# SSTuinoII_Jig.net
KiCad netlist of a schematic drawn in EAGLE
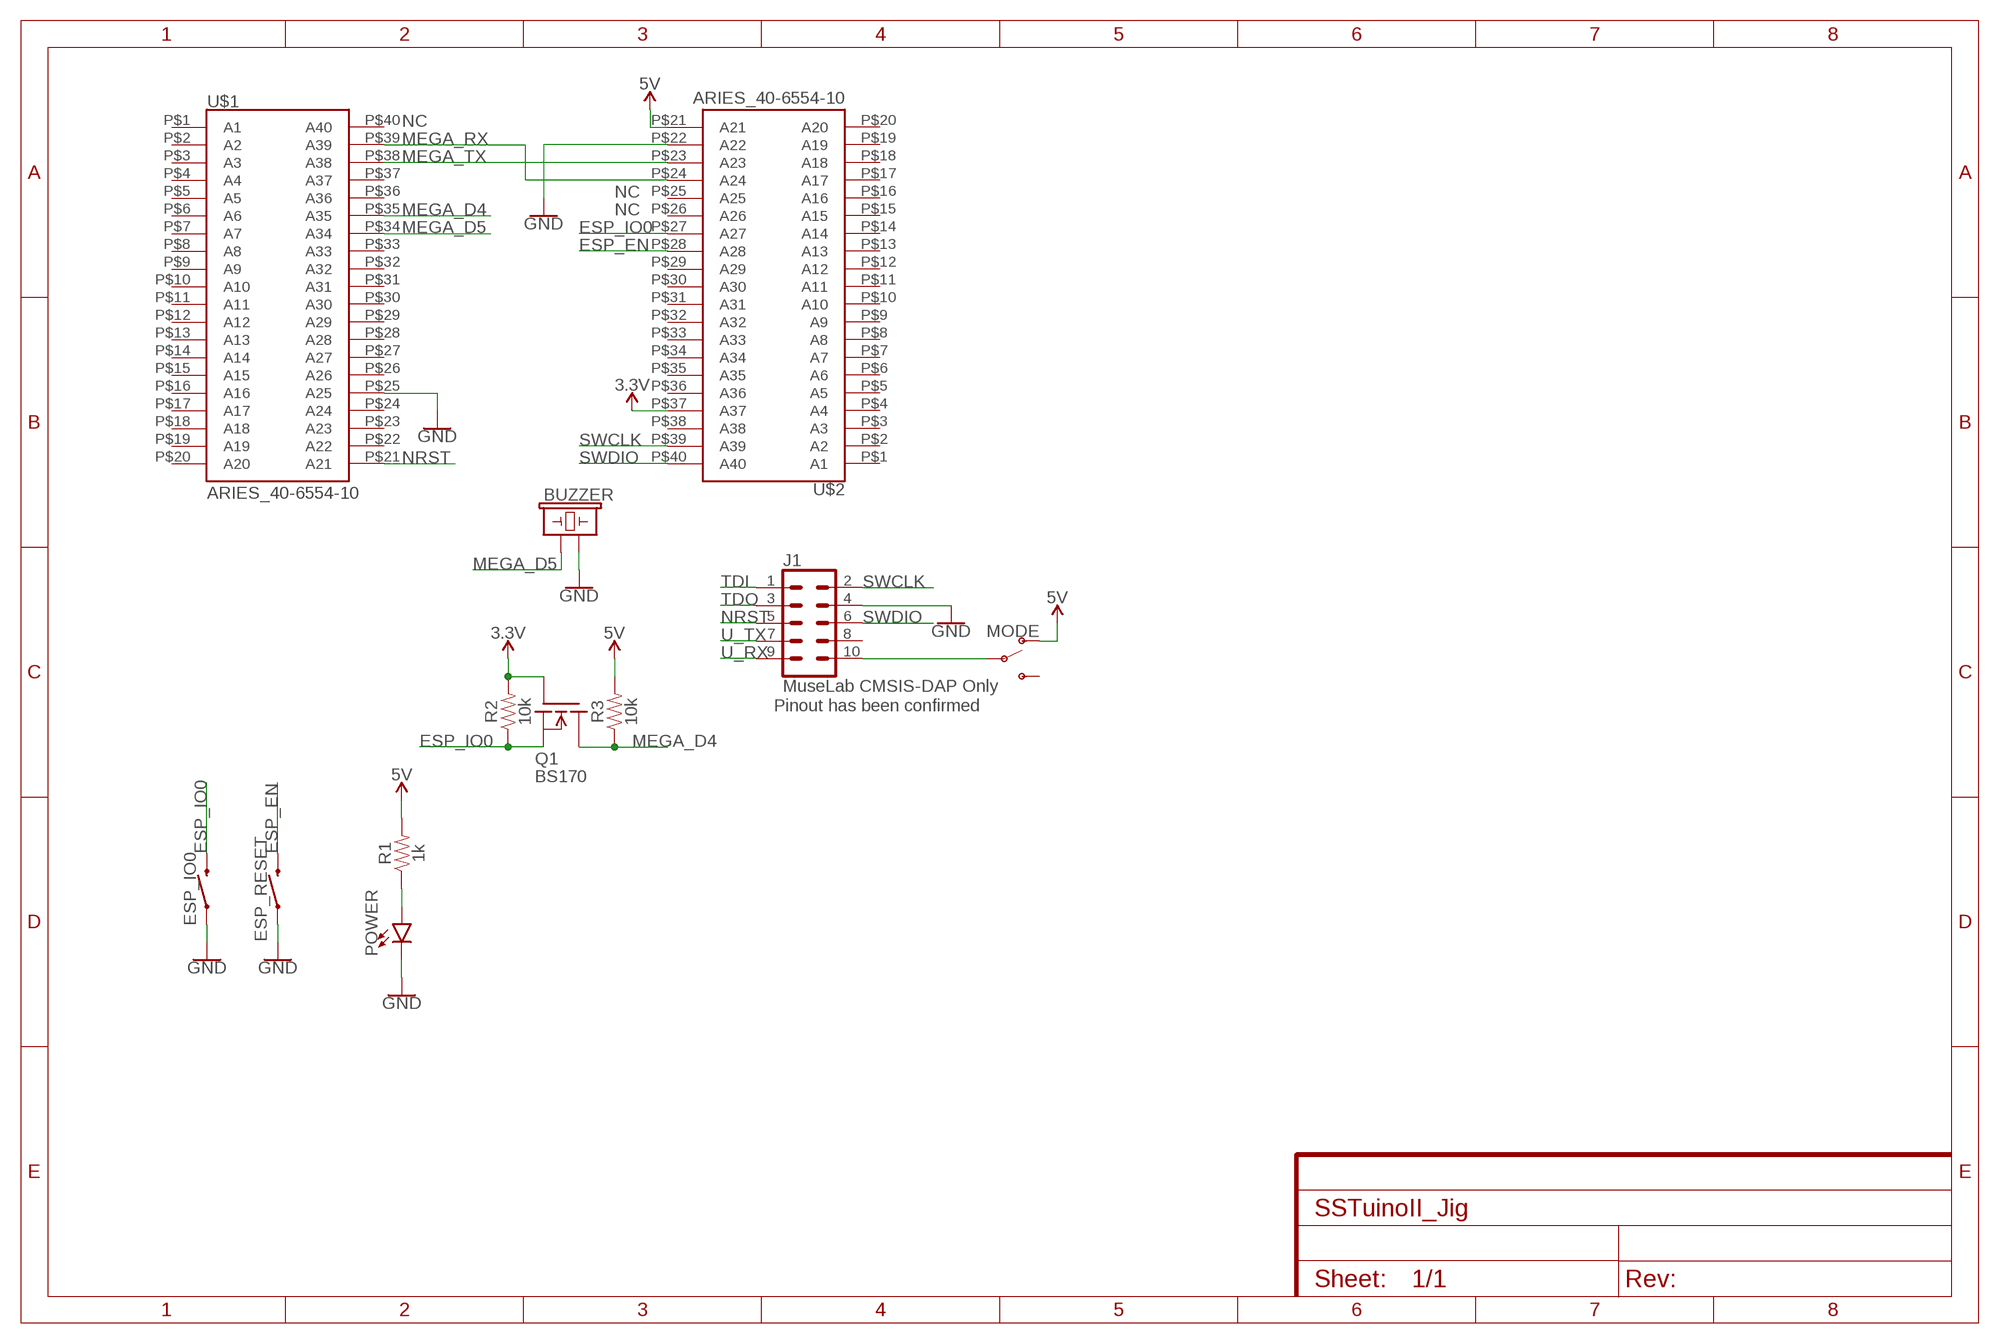
[diagram p0: schematic, sheet 1]

(export (version "E")
  (design (tool "Eeschema 10.0.6"))
  (components
    (comp (ref "BUZZER")
      (value "BUZZER-PTH_KIT")
      (footprint "eagle-import:BUZZER-12MM-KIT")
      (libsource (lib "eagle-import") (part "BUZZER-PTH_KIT"))
    )
    (comp (ref "ESP_IO0")
      (value "MOMENTARY-SWITCH-SPST-PTH-6.0MM-KIT")
      (footprint "eagle-import:TACTILE_SWITCH_PTH_6.0MM_KIT")
      (libsource (lib "eagle-import") (part "MOMENTARY-SWITCH-SPST-PTH-6.0MM-KIT"))
    )
    (comp (ref "ESP_RESET")
      (value "MOMENTARY-SWITCH-SPST-PTH-6.0MM-KIT")
      (footprint "eagle-import:TACTILE_SWITCH_PTH_6.0MM_KIT")
      (libsource (lib "eagle-import") (part "MOMENTARY-SWITCH-SPST-PTH-6.0MM-KIT"))
    )
    (comp (ref "J1")
      (value "MuseLab CMSIS-DAP Only")
      (footprint "eagle-import:2X5-SHROUDED_LOCK")
      (libsource (lib "eagle-import") (part "CONN_05X2SHD_LOCK"))
    )
    (comp (ref "MODE")
      (value "SWITCH-SPDT-PTH-11.6X4.0MM-KIT")
      (footprint "eagle-import:SWITCH_SPDT_PTH_11.6X4.0MM_KIT")
      (libsource (lib "eagle-import") (part "SWITCH-SPDT-PTH-11.6X4.0MM-KIT"))
    )
    (comp (ref "POWER")
      (value "LED3MM")
      (footprint "eagle-import:LED_3MM")
      (libsource (lib "eagle-import") (part "LED3MM"))
    )
    (comp (ref "Q1")
      (value "BS170")
      (footprint "eagle-import:TO92")
      (libsource (lib "eagle-import") (part "BSS101"))
    )
    (comp (ref "R1")
      (value "1k")
      (footprint "eagle-import:AXIAL-0.3-KIT")
      (libsource (lib "eagle-import") (part "1KOHM-HORIZ_KIT-1/4W-1%"))
    )
    (comp (ref "R2")
      (value "10k")
      (footprint "eagle-import:AXIAL-0.3-KIT")
      (libsource (lib "eagle-import") (part "10KOHM-HORIZ_KIT-1/4W-1%"))
    )
    (comp (ref "R3")
      (value "10k")
      (footprint "eagle-import:AXIAL-0.3-KIT")
      (libsource (lib "eagle-import") (part "10KOHM-HORIZ_KIT-1/4W-1%"))
    )
    (comp (ref "U$1")
      (value "ARIES_40-6554-10")
      (footprint "eagle-import:ARIES_40-6554-10")
      (libsource (lib "eagle-import") (part "ARIES_40-6554-10"))
    )
    (comp (ref "U$2")
      (value "ARIES_40-6554-10")
      (footprint "eagle-import:ARIES_40-6554-10")
      (libsource (lib "eagle-import") (part "ARIES_40-6554-10"))
    )
  )
  (nets
    (net (code "1") (name "/ESP_EN") (class "Default")
      (node (ref "ESP_RESET") (pin "3") (pinfunction "2_3") (pintype "passive"))
      (node (ref "U$2") (pin "P$28") (pinfunction "A28_P$28") (pintype "bidirectional"))
    )
    (net (code "2") (name "/ESP_IO0") (class "Default")
      (node (ref "ESP_IO0") (pin "3") (pinfunction "2_3") (pintype "passive"))
      (node (ref "Q1") (pin "1") (pinfunction "S_1") (pintype "passive"))
      (node (ref "R2") (pin "P$1") (pinfunction "1_P$1") (pintype "passive"))
      (node (ref "U$2") (pin "P$27") (pinfunction "A27_P$27") (pintype "bidirectional"))
    )
    (net (code "3") (name "/MEGA_D4") (class "Default")
      (node (ref "Q1") (pin "3") (pinfunction "D_3") (pintype "passive"))
      (node (ref "R3") (pin "P$1") (pinfunction "1_P$1") (pintype "passive"))
      (node (ref "U$1") (pin "P$35") (pinfunction "A35_P$35") (pintype "bidirectional"))
    )
    (net (code "4") (name "/MEGA_D5") (class "Default")
      (node (ref "BUZZER") (pin "+") (pinfunction "1_+") (pintype "passive"))
      (node (ref "U$1") (pin "P$34") (pinfunction "A34_P$34") (pintype "bidirectional"))
    )
    (net (code "5") (name "/MEGA_RX") (class "Default")
      (node (ref "U$1") (pin "P$39") (pinfunction "A39_P$39") (pintype "bidirectional"))
      (node (ref "U$2") (pin "P$24") (pinfunction "A24_P$24") (pintype "bidirectional"))
    )
    (net (code "6") (name "/MEGA_TX") (class "Default")
      (node (ref "U$1") (pin "P$38") (pinfunction "A38_P$38") (pintype "bidirectional"))
      (node (ref "U$2") (pin "P$23") (pinfunction "A23_P$23") (pintype "bidirectional"))
    )
    (net (code "7") (name "/NRST") (class "Default")
      (node (ref "J1") (pin "5") (pinfunction "5_5") (pintype "passive"))
      (node (ref "U$1") (pin "P$21") (pinfunction "A21_P$21") (pintype "bidirectional"))
    )
    (net (code "8") (name "/SWCLK") (class "Default")
      (node (ref "J1") (pin "2") (pinfunction "2_2") (pintype "passive"))
      (node (ref "U$2") (pin "P$39") (pinfunction "A39_P$39") (pintype "bidirectional"))
    )
    (net (code "9") (name "/SWDIO") (class "Default")
      (node (ref "J1") (pin "6") (pinfunction "6_6") (pintype "passive"))
      (node (ref "U$2") (pin "P$40") (pinfunction "A40_P$40") (pintype "bidirectional"))
    )
    (net (code "10") (name "/TDI") (class "Default")
      (node (ref "J1") (pin "1") (pinfunction "1_1") (pintype "passive"))
    )
    (net (code "11") (name "/TDO") (class "Default")
      (node (ref "J1") (pin "3") (pinfunction "3_3") (pintype "passive"))
    )
    (net (code "12") (name "/U_RX") (class "Default")
      (node (ref "J1") (pin "9") (pinfunction "9_9") (pintype "passive"))
    )
    (net (code "13") (name "/U_TX") (class "Default")
      (node (ref "J1") (pin "7") (pinfunction "7_7") (pintype "passive"))
    )
    (net (code "14") (name "3.3V") (class "Default")
      (node (ref "Q1") (pin "2") (pinfunction "G_2") (pintype "passive"))
      (node (ref "R2") (pin "P$2") (pinfunction "2_P$2") (pintype "passive"))
      (node (ref "U$2") (pin "P$37") (pinfunction "A37_P$37") (pintype "bidirectional"))
    )
    (net (code "15") (name "5V") (class "Default")
      (node (ref "MODE") (pin "1") (pinfunction "O_1") (pintype "passive"))
      (node (ref "R1") (pin "P$2") (pinfunction "2_P$2") (pintype "passive"))
      (node (ref "R3") (pin "P$2") (pinfunction "2_P$2") (pintype "passive"))
      (node (ref "U$2") (pin "P$21") (pinfunction "A21_P$21") (pintype "bidirectional"))
    )
    (net (code "16") (name "GND") (class "Default")
      (node (ref "BUZZER") (pin "-") (pinfunction "2_-") (pintype "passive"))
      (node (ref "ESP_IO0") (pin "1") (pinfunction "1_1") (pintype "passive"))
      (node (ref "ESP_RESET") (pin "1") (pinfunction "1_1") (pintype "passive"))
      (node (ref "J1") (pin "4") (pinfunction "4_4") (pintype "passive"))
      (node (ref "POWER") (pin "K") (pinfunction "C_K") (pintype "passive"))
      (node (ref "U$1") (pin "P$25") (pinfunction "A25_P$25") (pintype "bidirectional"))
      (node (ref "U$2") (pin "P$22") (pinfunction "A22_P$22") (pintype "bidirectional"))
    )
    (net (code "17") (name "Net-(MODE-P)") (class "Default")
      (node (ref "J1") (pin "10") (pinfunction "10_10") (pintype "passive"))
      (node (ref "MODE") (pin "2") (pinfunction "P_2") (pintype "passive"))
    )
    (net (code "18") (name "Net-(R1-1)") (class "Default")
      (node (ref "POWER") (pin "A") (pinfunction "A_A") (pintype "passive"))
      (node (ref "R1") (pin "P$1") (pinfunction "1_P$1") (pintype "passive"))
    )
    (net (code "19") (name "unconnected-(J1-Pad8)") (class "Default")
      (node (ref "J1") (pin "8") (pinfunction "8_8") (pintype "passive"))
    )
    (net (code "20") (name "unconnected-(MODE-S-Pad3)") (class "Default")
      (node (ref "MODE") (pin "3") (pinfunction "S_3") (pintype "passive"))
    )
    (net (code "21") (name "unconnected-(U$1-A1-PadP$1)") (class "Default")
      (node (ref "U$1") (pin "P$1") (pinfunction "A1_P$1") (pintype "bidirectional"))
    )
    (net (code "22") (name "unconnected-(U$1-A2-PadP$2)") (class "Default")
      (node (ref "U$1") (pin "P$2") (pinfunction "A2_P$2") (pintype "bidirectional"))
    )
    (net (code "23") (name "unconnected-(U$1-A3-PadP$3)") (class "Default")
      (node (ref "U$1") (pin "P$3") (pinfunction "A3_P$3") (pintype "bidirectional"))
    )
    (net (code "24") (name "unconnected-(U$1-A4-PadP$4)") (class "Default")
      (node (ref "U$1") (pin "P$4") (pinfunction "A4_P$4") (pintype "bidirectional"))
    )
    (net (code "25") (name "unconnected-(U$1-A5-PadP$5)") (class "Default")
      (node (ref "U$1") (pin "P$5") (pinfunction "A5_P$5") (pintype "bidirectional"))
    )
    (net (code "26") (name "unconnected-(U$1-A6-PadP$6)") (class "Default")
      (node (ref "U$1") (pin "P$6") (pinfunction "A6_P$6") (pintype "bidirectional"))
    )
    (net (code "27") (name "unconnected-(U$1-A7-PadP$7)") (class "Default")
      (node (ref "U$1") (pin "P$7") (pinfunction "A7_P$7") (pintype "bidirectional"))
    )
    (net (code "28") (name "unconnected-(U$1-A8-PadP$8)") (class "Default")
      (node (ref "U$1") (pin "P$8") (pinfunction "A8_P$8") (pintype "bidirectional"))
    )
    (net (code "29") (name "unconnected-(U$1-A9-PadP$9)") (class "Default")
      (node (ref "U$1") (pin "P$9") (pinfunction "A9_P$9") (pintype "bidirectional"))
    )
    (net (code "30") (name "unconnected-(U$1-A10-PadP$10)") (class "Default")
      (node (ref "U$1") (pin "P$10") (pinfunction "A10_P$10") (pintype "bidirectional"))
    )
    (net (code "31") (name "unconnected-(U$1-A11-PadP$11)") (class "Default")
      (node (ref "U$1") (pin "P$11") (pinfunction "A11_P$11") (pintype "bidirectional"))
    )
    (net (code "32") (name "unconnected-(U$1-A12-PadP$12)") (class "Default")
      (node (ref "U$1") (pin "P$12") (pinfunction "A12_P$12") (pintype "bidirectional"))
    )
    (net (code "33") (name "unconnected-(U$1-A13-PadP$13)") (class "Default")
      (node (ref "U$1") (pin "P$13") (pinfunction "A13_P$13") (pintype "bidirectional"))
    )
    (net (code "34") (name "unconnected-(U$1-A14-PadP$14)") (class "Default")
      (node (ref "U$1") (pin "P$14") (pinfunction "A14_P$14") (pintype "bidirectional"))
    )
    (net (code "35") (name "unconnected-(U$1-A15-PadP$15)") (class "Default")
      (node (ref "U$1") (pin "P$15") (pinfunction "A15_P$15") (pintype "bidirectional"))
    )
    (net (code "36") (name "unconnected-(U$1-A16-PadP$16)") (class "Default")
      (node (ref "U$1") (pin "P$16") (pinfunction "A16_P$16") (pintype "bidirectional"))
    )
    (net (code "37") (name "unconnected-(U$1-A17-PadP$17)") (class "Default")
      (node (ref "U$1") (pin "P$17") (pinfunction "A17_P$17") (pintype "bidirectional"))
    )
    (net (code "38") (name "unconnected-(U$1-A18-PadP$18)") (class "Default")
      (node (ref "U$1") (pin "P$18") (pinfunction "A18_P$18") (pintype "bidirectional"))
    )
    (net (code "39") (name "unconnected-(U$1-A19-PadP$19)") (class "Default")
      (node (ref "U$1") (pin "P$19") (pinfunction "A19_P$19") (pintype "bidirectional"))
    )
    (net (code "40") (name "unconnected-(U$1-A20-PadP$20)") (class "Default")
      (node (ref "U$1") (pin "P$20") (pinfunction "A20_P$20") (pintype "bidirectional"))
    )
    (net (code "41") (name "unconnected-(U$1-A22-PadP$22)") (class "Default")
      (node (ref "U$1") (pin "P$22") (pinfunction "A22_P$22") (pintype "bidirectional"))
    )
    (net (code "42") (name "unconnected-(U$1-A23-PadP$23)") (class "Default")
      (node (ref "U$1") (pin "P$23") (pinfunction "A23_P$23") (pintype "bidirectional"))
    )
    (net (code "43") (name "unconnected-(U$1-A24-PadP$24)") (class "Default")
      (node (ref "U$1") (pin "P$24") (pinfunction "A24_P$24") (pintype "bidirectional"))
    )
    (net (code "44") (name "unconnected-(U$1-A26-PadP$26)") (class "Default")
      (node (ref "U$1") (pin "P$26") (pinfunction "A26_P$26") (pintype "bidirectional"))
    )
    (net (code "45") (name "unconnected-(U$1-A27-PadP$27)") (class "Default")
      (node (ref "U$1") (pin "P$27") (pinfunction "A27_P$27") (pintype "bidirectional"))
    )
    (net (code "46") (name "unconnected-(U$1-A28-PadP$28)") (class "Default")
      (node (ref "U$1") (pin "P$28") (pinfunction "A28_P$28") (pintype "bidirectional"))
    )
    (net (code "47") (name "unconnected-(U$1-A29-PadP$29)") (class "Default")
      (node (ref "U$1") (pin "P$29") (pinfunction "A29_P$29") (pintype "bidirectional"))
    )
    (net (code "48") (name "unconnected-(U$1-A30-PadP$30)") (class "Default")
      (node (ref "U$1") (pin "P$30") (pinfunction "A30_P$30") (pintype "bidirectional"))
    )
    (net (code "49") (name "unconnected-(U$1-A31-PadP$31)") (class "Default")
      (node (ref "U$1") (pin "P$31") (pinfunction "A31_P$31") (pintype "bidirectional"))
    )
    (net (code "50") (name "unconnected-(U$1-A32-PadP$32)") (class "Default")
      (node (ref "U$1") (pin "P$32") (pinfunction "A32_P$32") (pintype "bidirectional"))
    )
    (net (code "51") (name "unconnected-(U$1-A33-PadP$33)") (class "Default")
      (node (ref "U$1") (pin "P$33") (pinfunction "A33_P$33") (pintype "bidirectional"))
    )
    (net (code "52") (name "unconnected-(U$1-A36-PadP$36)") (class "Default")
      (node (ref "U$1") (pin "P$36") (pinfunction "A36_P$36") (pintype "bidirectional"))
    )
    (net (code "53") (name "unconnected-(U$1-A37-PadP$37)") (class "Default")
      (node (ref "U$1") (pin "P$37") (pinfunction "A37_P$37") (pintype "bidirectional"))
    )
    (net (code "54") (name "unconnected-(U$1-A40-PadP$40)") (class "Default")
      (node (ref "U$1") (pin "P$40") (pinfunction "A40_P$40") (pintype "bidirectional"))
    )
    (net (code "55") (name "unconnected-(U$2-A1-PadP$1)") (class "Default")
      (node (ref "U$2") (pin "P$1") (pinfunction "A1_P$1") (pintype "bidirectional"))
    )
    (net (code "56") (name "unconnected-(U$2-A2-PadP$2)") (class "Default")
      (node (ref "U$2") (pin "P$2") (pinfunction "A2_P$2") (pintype "bidirectional"))
    )
    (net (code "57") (name "unconnected-(U$2-A3-PadP$3)") (class "Default")
      (node (ref "U$2") (pin "P$3") (pinfunction "A3_P$3") (pintype "bidirectional"))
    )
    (net (code "58") (name "unconnected-(U$2-A4-PadP$4)") (class "Default")
      (node (ref "U$2") (pin "P$4") (pinfunction "A4_P$4") (pintype "bidirectional"))
    )
    (net (code "59") (name "unconnected-(U$2-A5-PadP$5)") (class "Default")
      (node (ref "U$2") (pin "P$5") (pinfunction "A5_P$5") (pintype "bidirectional"))
    )
    (net (code "60") (name "unconnected-(U$2-A6-PadP$6)") (class "Default")
      (node (ref "U$2") (pin "P$6") (pinfunction "A6_P$6") (pintype "bidirectional"))
    )
    (net (code "61") (name "unconnected-(U$2-A7-PadP$7)") (class "Default")
      (node (ref "U$2") (pin "P$7") (pinfunction "A7_P$7") (pintype "bidirectional"))
    )
    (net (code "62") (name "unconnected-(U$2-A8-PadP$8)") (class "Default")
      (node (ref "U$2") (pin "P$8") (pinfunction "A8_P$8") (pintype "bidirectional"))
    )
    (net (code "63") (name "unconnected-(U$2-A9-PadP$9)") (class "Default")
      (node (ref "U$2") (pin "P$9") (pinfunction "A9_P$9") (pintype "bidirectional"))
    )
    (net (code "64") (name "unconnected-(U$2-A10-PadP$10)") (class "Default")
      (node (ref "U$2") (pin "P$10") (pinfunction "A10_P$10") (pintype "bidirectional"))
    )
    (net (code "65") (name "unconnected-(U$2-A11-PadP$11)") (class "Default")
      (node (ref "U$2") (pin "P$11") (pinfunction "A11_P$11") (pintype "bidirectional"))
    )
    (net (code "66") (name "unconnected-(U$2-A12-PadP$12)") (class "Default")
      (node (ref "U$2") (pin "P$12") (pinfunction "A12_P$12") (pintype "bidirectional"))
    )
    (net (code "67") (name "unconnected-(U$2-A13-PadP$13)") (class "Default")
      (node (ref "U$2") (pin "P$13") (pinfunction "A13_P$13") (pintype "bidirectional"))
    )
    (net (code "68") (name "unconnected-(U$2-A14-PadP$14)") (class "Default")
      (node (ref "U$2") (pin "P$14") (pinfunction "A14_P$14") (pintype "bidirectional"))
    )
    (net (code "69") (name "unconnected-(U$2-A15-PadP$15)") (class "Default")
      (node (ref "U$2") (pin "P$15") (pinfunction "A15_P$15") (pintype "bidirectional"))
    )
    (net (code "70") (name "unconnected-(U$2-A16-PadP$16)") (class "Default")
      (node (ref "U$2") (pin "P$16") (pinfunction "A16_P$16") (pintype "bidirectional"))
    )
    (net (code "71") (name "unconnected-(U$2-A17-PadP$17)") (class "Default")
      (node (ref "U$2") (pin "P$17") (pinfunction "A17_P$17") (pintype "bidirectional"))
    )
    (net (code "72") (name "unconnected-(U$2-A18-PadP$18)") (class "Default")
      (node (ref "U$2") (pin "P$18") (pinfunction "A18_P$18") (pintype "bidirectional"))
    )
    (net (code "73") (name "unconnected-(U$2-A19-PadP$19)") (class "Default")
      (node (ref "U$2") (pin "P$19") (pinfunction "A19_P$19") (pintype "bidirectional"))
    )
    (net (code "74") (name "unconnected-(U$2-A20-PadP$20)") (class "Default")
      (node (ref "U$2") (pin "P$20") (pinfunction "A20_P$20") (pintype "bidirectional"))
    )
    (net (code "75") (name "unconnected-(U$2-A25-PadP$25)") (class "Default")
      (node (ref "U$2") (pin "P$25") (pinfunction "A25_P$25") (pintype "bidirectional"))
    )
    (net (code "76") (name "unconnected-(U$2-A26-PadP$26)") (class "Default")
      (node (ref "U$2") (pin "P$26") (pinfunction "A26_P$26") (pintype "bidirectional"))
    )
    (net (code "77") (name "unconnected-(U$2-A29-PadP$29)") (class "Default")
      (node (ref "U$2") (pin "P$29") (pinfunction "A29_P$29") (pintype "bidirectional"))
    )
    (net (code "78") (name "unconnected-(U$2-A30-PadP$30)") (class "Default")
      (node (ref "U$2") (pin "P$30") (pinfunction "A30_P$30") (pintype "bidirectional"))
    )
    (net (code "79") (name "unconnected-(U$2-A31-PadP$31)") (class "Default")
      (node (ref "U$2") (pin "P$31") (pinfunction "A31_P$31") (pintype "bidirectional"))
    )
    (net (code "80") (name "unconnected-(U$2-A32-PadP$32)") (class "Default")
      (node (ref "U$2") (pin "P$32") (pinfunction "A32_P$32") (pintype "bidirectional"))
    )
    (net (code "81") (name "unconnected-(U$2-A33-PadP$33)") (class "Default")
      (node (ref "U$2") (pin "P$33") (pinfunction "A33_P$33") (pintype "bidirectional"))
    )
    (net (code "82") (name "unconnected-(U$2-A34-PadP$34)") (class "Default")
      (node (ref "U$2") (pin "P$34") (pinfunction "A34_P$34") (pintype "bidirectional"))
    )
    (net (code "83") (name "unconnected-(U$2-A35-PadP$35)") (class "Default")
      (node (ref "U$2") (pin "P$35") (pinfunction "A35_P$35") (pintype "bidirectional"))
    )
    (net (code "84") (name "unconnected-(U$2-A36-PadP$36)") (class "Default")
      (node (ref "U$2") (pin "P$36") (pinfunction "A36_P$36") (pintype "bidirectional"))
    )
    (net (code "85") (name "unconnected-(U$2-A38-PadP$38)") (class "Default")
      (node (ref "U$2") (pin "P$38") (pinfunction "A38_P$38") (pintype "bidirectional"))
    )
  )
)
